# mate_a.net
KiCad netlist of a schematic drawn in EAGLE
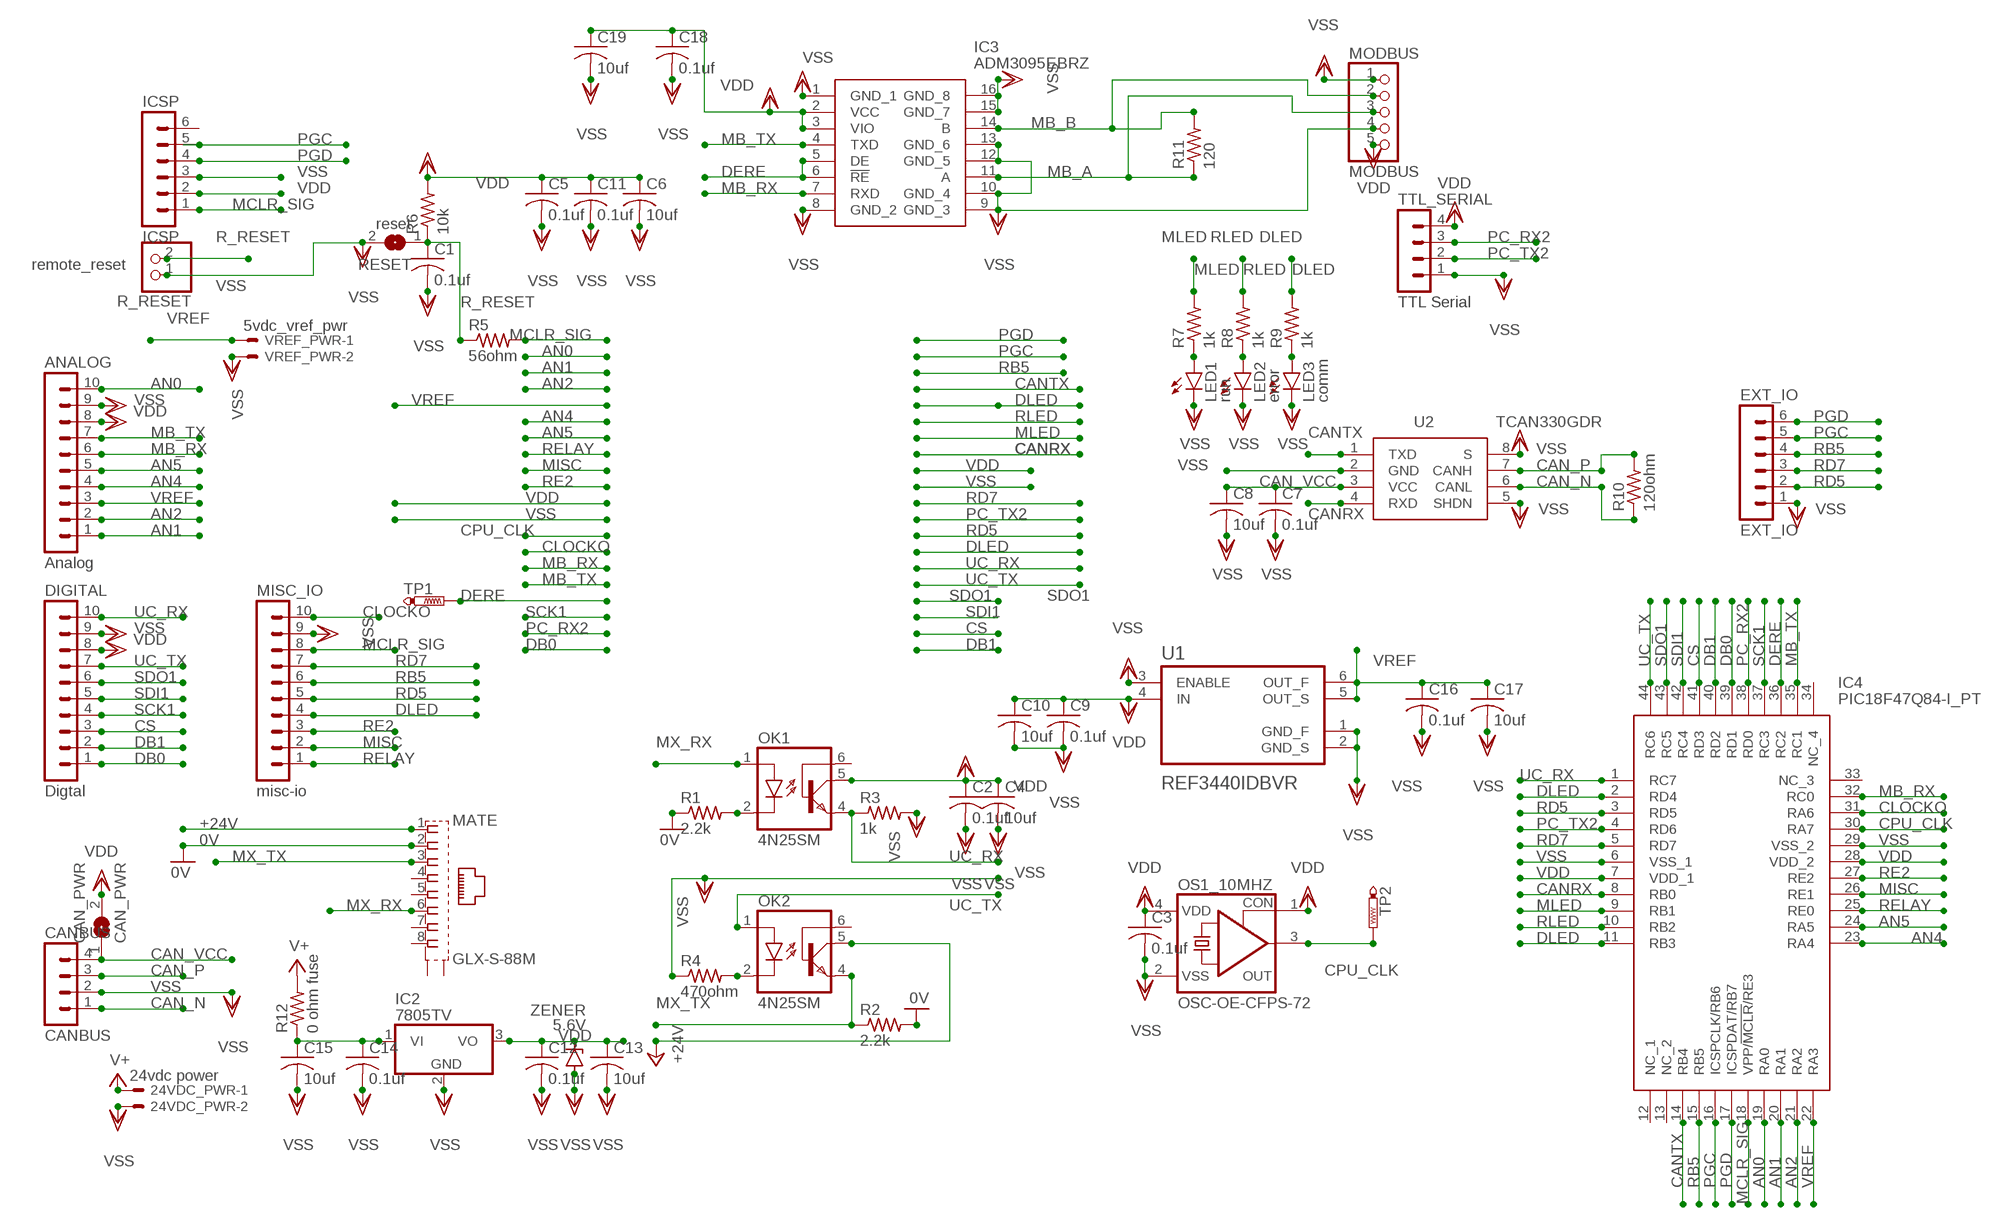
[diagram p0: schematic, sheet 1]

(export (version "E")
  (design (tool "Eeschema 10.0.6"))
  (components
    (comp (ref "24VDC_PWR")
      (value "24vdc power")
      (footprint "eagle-import:22-23-2021")
      (fields (field (name "MF") "MOLEX") (field (name "MPN") "22-23-2021"))
      (libsource (lib "eagle-import") (part "22-23-2021"))
    )
    (comp (ref "ANALOG")
      (value "Analog")
      (footprint "eagle-import:MA10-1")
      (libsource (lib "eagle-import") (part "MA10-1"))
    )
    (comp (ref "C1")
      (value "0.1uf")
      (footprint "eagle-import:C0805")
      (libsource (lib "eagle-import") (part "C-USC0805"))
    )
    (comp (ref "C2")
      (value "0.1uf")
      (footprint "eagle-import:C0805")
      (libsource (lib "eagle-import") (part "C-USC0805"))
    )
    (comp (ref "C3")
      (value "0.1uf")
      (footprint "eagle-import:C0805")
      (libsource (lib "eagle-import") (part "C-USC0805"))
    )
    (comp (ref "C4")
      (value "10uf")
      (footprint "eagle-import:C0805")
      (libsource (lib "eagle-import") (part "C-USC0805"))
    )
    (comp (ref "C5")
      (value "0.1uf")
      (footprint "eagle-import:C0805")
      (libsource (lib "eagle-import") (part "C-USC0805"))
    )
    (comp (ref "C6")
      (value "10uf")
      (footprint "eagle-import:C0805")
      (libsource (lib "eagle-import") (part "C-USC0805"))
    )
    (comp (ref "C7")
      (value "0.1uf")
      (footprint "eagle-import:C0805")
      (libsource (lib "eagle-import") (part "C-USC0805"))
    )
    (comp (ref "C8")
      (value "10uf")
      (footprint "eagle-import:C0805")
      (libsource (lib "eagle-import") (part "C-USC0805"))
    )
    (comp (ref "C9")
      (value "0.1uf")
      (footprint "eagle-import:C0805")
      (libsource (lib "eagle-import") (part "C-USC0805"))
    )
    (comp (ref "C10")
      (value "10uf")
      (footprint "eagle-import:C0805")
      (libsource (lib "eagle-import") (part "C-USC0805"))
    )
    (comp (ref "C11")
      (value "0.1uf")
      (footprint "eagle-import:C0805")
      (libsource (lib "eagle-import") (part "C-USC0805"))
    )
    (comp (ref "C12")
      (value "0.1uf")
      (footprint "eagle-import:C0805")
      (libsource (lib "eagle-import") (part "C-USC0805"))
    )
    (comp (ref "C13")
      (value "10uf")
      (footprint "eagle-import:C0805")
      (libsource (lib "eagle-import") (part "C-USC0805"))
    )
    (comp (ref "C14")
      (value "0.1uf")
      (footprint "eagle-import:C0805")
      (libsource (lib "eagle-import") (part "C-USC0805"))
    )
    (comp (ref "C15")
      (value "10uf")
      (footprint "eagle-import:C0805")
      (libsource (lib "eagle-import") (part "C-USC0805"))
    )
    (comp (ref "C16")
      (value "0.1uf")
      (footprint "eagle-import:C0805")
      (libsource (lib "eagle-import") (part "C-USC0805"))
    )
    (comp (ref "C17")
      (value "10uf")
      (footprint "eagle-import:C0805")
      (libsource (lib "eagle-import") (part "C-USC0805"))
    )
    (comp (ref "C18")
      (value "0.1uf")
      (footprint "eagle-import:C0805")
      (libsource (lib "eagle-import") (part "C-USC0805"))
    )
    (comp (ref "C19")
      (value "10uf")
      (footprint "eagle-import:C0805")
      (libsource (lib "eagle-import") (part "C-USC0805"))
    )
    (comp (ref "CANBUS")
      (value "CANBUS")
      (footprint "eagle-import:MA04-1")
      (libsource (lib "eagle-import") (part "MA04-1"))
    )
    (comp (ref "CAN_PWR")
      (value "CAN_PWR")
      (footprint "eagle-import:SJ")
      (libsource (lib "eagle-import") (part "SJ"))
    )
    (comp (ref "DIGITAL")
      (value "Digtal")
      (footprint "eagle-import:MA10-1")
      (libsource (lib "eagle-import") (part "MA10-1"))
    )
    (comp (ref "EXT_IO")
      (value "EXT_IO")
      (footprint "eagle-import:MA06-1")
      (libsource (lib "eagle-import") (part "MA06-1"))
    )
    (comp (ref "IC2")
      (value "7805TV")
      (footprint "eagle-import:TO220V")
      (libsource (lib "eagle-import") (part "78TV05"))
    )
    (comp (ref "IC3")
      (value "ADM3095EBRZ")
      (footprint "eagle-import:SOIC127P600X175-16N")
      (fields (field (name "MOUSER_PART_NUMBER") "584-ADM3095EBRZ"))
      (libsource (lib "eagle-import") (part "ADM3095EBRZ"))
    )
    (comp (ref "IC4")
      (value "PIC18F47Q84-I_PT")
      (footprint "eagle-import:QFP80P1200X1200X120-44N")
      (fields
        (field (name "MANUFACTURER_PART_NUMBER") "PIC18F47Q84-I/PT")
        (field (name "MOUSER_PART_NUMBER") "579-PIC18F47Q84-I/PT")
      )
      (libsource (lib "eagle-import") (part "PIC18F47Q84-I_PT"))
    )
    (comp (ref "ICSP")
      (value "ICSP")
      (footprint "eagle-import:MA06-1")
      (libsource (lib "eagle-import") (part "MA06-1"))
    )
    (comp (ref "LED1")
      (value "run")
      (footprint "eagle-import:CHIPLED_0805")
      (libsource (lib "eagle-import") (part "LEDCHIPLED_0805"))
    )
    (comp (ref "LED2")
      (value "error")
      (footprint "eagle-import:CHIPLED_0805")
      (libsource (lib "eagle-import") (part "LEDCHIPLED_0805"))
    )
    (comp (ref "LED3")
      (value "comm")
      (footprint "eagle-import:CHIPLED_0805")
      (libsource (lib "eagle-import") (part "LEDCHIPLED_0805"))
    )
    (comp (ref "MATE")
      (value "GLX-S-88M")
      (footprint "eagle-import:GLX-S-88M")
      (libsource (lib "eagle-import") (part "GLX-S-88M"))
    )
    (comp (ref "MISC_IO")
      (value "misc-io")
      (footprint "eagle-import:MA10-1")
      (libsource (lib "eagle-import") (part "MA10-1"))
    )
    (comp (ref "MODBUS")
      (value "MODBUS")
      (footprint "eagle-import:1X05")
      (libsource (lib "eagle-import") (part "PINHD-1X5"))
    )
    (comp (ref "OK1")
      (value "4N25SM")
      (footprint "eagle-import:DIL6-SMD")
      (fields (field (name "MF") "FAIRCHILD SEMICONDUCTOR"))
      (libsource (lib "eagle-import") (part "4N?MS25"))
    )
    (comp (ref "OK2")
      (value "4N25SM")
      (footprint "eagle-import:DIL6-SMD")
      (fields (field (name "MF") "FAIRCHILD SEMICONDUCTOR"))
      (libsource (lib "eagle-import") (part "4N?MS25"))
    )
    (comp (ref "OS1_10MHZ")
      (value "OSC-OE-CFPS-72")
      (footprint "eagle-import:7.2X5.2-4-PAD")
      (libsource (lib "eagle-import") (part "OSC-OE-CFPS-72"))
    )
    (comp (ref "R1")
      (value "2.2k")
      (footprint "eagle-import:R0805")
      (libsource (lib "eagle-import") (part "R-US_R0805"))
    )
    (comp (ref "R2")
      (value "2.2k")
      (footprint "eagle-import:R0805")
      (libsource (lib "eagle-import") (part "R-US_R0805"))
    )
    (comp (ref "R3")
      (value "1k")
      (footprint "eagle-import:R0805")
      (libsource (lib "eagle-import") (part "R-US_R0805"))
    )
    (comp (ref "R4")
      (value "470ohm")
      (footprint "eagle-import:R0805")
      (libsource (lib "eagle-import") (part "R-US_R0805"))
    )
    (comp (ref "R5")
      (value "56ohm")
      (footprint "eagle-import:R0805")
      (libsource (lib "eagle-import") (part "R-US_R0805"))
    )
    (comp (ref "R6")
      (value "10k")
      (footprint "eagle-import:R0805")
      (libsource (lib "eagle-import") (part "R-US_R0805"))
    )
    (comp (ref "R7")
      (value "1k")
      (footprint "eagle-import:R0805")
      (libsource (lib "eagle-import") (part "R-US_R0805"))
    )
    (comp (ref "R8")
      (value "1k")
      (footprint "eagle-import:R0805")
      (libsource (lib "eagle-import") (part "R-US_R0805"))
    )
    (comp (ref "R9")
      (value "1k")
      (footprint "eagle-import:R0805")
      (libsource (lib "eagle-import") (part "R-US_R0805"))
    )
    (comp (ref "R10")
      (value "120ohm")
      (footprint "eagle-import:R0805")
      (libsource (lib "eagle-import") (part "R-US_R0805"))
    )
    (comp (ref "R11")
      (value "120")
      (footprint "eagle-import:R0805")
      (libsource (lib "eagle-import") (part "R-US_R0805"))
    )
    (comp (ref "R12")
      (value "0 ohm fuse")
      (footprint "eagle-import:R1206")
      (libsource (lib "eagle-import") (part "R-US_R1206"))
    )
    (comp (ref "RESET")
      (value "reset")
      (footprint "eagle-import:SJ")
      (libsource (lib "eagle-import") (part "SJ"))
    )
    (comp (ref "R_RESET")
      (value "remote_reset")
      (footprint "eagle-import:1X02")
      (libsource (lib "eagle-import") (part "PINHD-1X2"))
    )
    (comp (ref "TP1")
      (value "PTR1PAD1-13")
      (footprint "eagle-import:P1-13")
      (libsource (lib "eagle-import") (part "PTR1PAD1-13"))
    )
    (comp (ref "TP2")
      (value "PTR1PAD1-13")
      (footprint "eagle-import:P1-13")
      (libsource (lib "eagle-import") (part "PTR1PAD1-13"))
    )
    (comp (ref "TTL_SERIAL")
      (value "TTL Serial")
      (footprint "eagle-import:MA04-1")
      (libsource (lib "eagle-import") (part "MA04-1"))
    )
    (comp (ref "U1")
      (value "REF3440IDBVR")
      (footprint "eagle-import:SOT95P280X145-6N")
      (fields (field (name "MF") "Texas Instruments"))
      (libsource (lib "eagle-import") (part "REF3440IDBVR"))
    )
    (comp (ref "U2")
      (value "TCAN330GDR")
      (footprint "eagle-import:SOIC127P600X175-8N")
      (fields (field (name "MOUSER_PART_NUMBER") "595-TCAN330GDR"))
      (libsource (lib "eagle-import") (part "TCAN330GDR"))
    )
    (comp (ref "VREF_PWR")
      (value "5vdc_vref_pwr")
      (footprint "eagle-import:22-23-2021")
      (fields (field (name "MF") "MOLEX") (field (name "MPN") "22-23-2021"))
      (libsource (lib "eagle-import") (part "22-23-2021"))
    )
    (comp (ref "ZENER")
      (value "5.6V")
      (footprint "eagle-import:SMB")
      (libsource (lib "eagle-import") (part "ZENER-DIODESMB"))
    )
  )
  (nets
    (net (code "1") (name "+24V") (class "Default")
      (node (ref "MATE") (pin "1") (pinfunction "1_1") (pintype "passive"))
      (node (ref "OK2") (pin "5") (pinfunction "COL_5") (pintype "passive"))
    )
    (net (code "2") (name "/AN0") (class "Default")
      (node (ref "ANALOG") (pin "10") (pinfunction "10_10") (pintype "passive"))
      (node (ref "IC4") (pin "19") (pinfunction "RA0_19") (pintype "bidirectional"))
    )
    (net (code "3") (name "/AN1") (class "Default")
      (node (ref "ANALOG") (pin "1") (pinfunction "1_1") (pintype "passive"))
      (node (ref "IC4") (pin "20") (pinfunction "RA1_20") (pintype "bidirectional"))
    )
    (net (code "4") (name "/AN2") (class "Default")
      (node (ref "ANALOG") (pin "2") (pinfunction "2_2") (pintype "passive"))
      (node (ref "IC4") (pin "21") (pinfunction "RA2_21") (pintype "bidirectional"))
    )
    (net (code "5") (name "/AN4") (class "Default")
      (node (ref "ANALOG") (pin "4") (pinfunction "4_4") (pintype "passive"))
      (node (ref "IC4") (pin "23") (pinfunction "RA4_23") (pintype "bidirectional"))
    )
    (net (code "6") (name "/AN5") (class "Default")
      (node (ref "ANALOG") (pin "5") (pinfunction "5_5") (pintype "passive"))
      (node (ref "IC4") (pin "24") (pinfunction "RA5_24") (pintype "bidirectional"))
    )
    (net (code "7") (name "/CANRX") (class "Default")
      (node (ref "IC4") (pin "8") (pinfunction "RB0_8") (pintype "bidirectional"))
      (node (ref "U2") (pin "4") (pinfunction "RXD_4") (pintype "output"))
    )
    (net (code "8") (name "/CANTX") (class "Default")
      (node (ref "IC4") (pin "14") (pinfunction "RB4_14") (pintype "bidirectional"))
      (node (ref "U2") (pin "1") (pinfunction "TXD_1") (pintype "input"))
    )
    (net (code "9") (name "/CAN_N") (class "Default")
      (node (ref "CANBUS") (pin "1") (pinfunction "1_1") (pintype "passive"))
      (node (ref "R10") (pin "1") (pinfunction "1_1") (pintype "passive"))
      (node (ref "U2") (pin "6") (pinfunction "CANL_6") (pintype "bidirectional"))
    )
    (net (code "10") (name "/CAN_P") (class "Default")
      (node (ref "CANBUS") (pin "3") (pinfunction "3_3") (pintype "passive"))
      (node (ref "R10") (pin "2") (pinfunction "2_2") (pintype "passive"))
      (node (ref "U2") (pin "7") (pinfunction "CANH_7") (pintype "bidirectional"))
    )
    (net (code "11") (name "/CAN_VCC") (class "Default")
      (node (ref "C7") (pin "1") (pinfunction "1_1") (pintype "passive"))
      (node (ref "C8") (pin "1") (pinfunction "1_1") (pintype "passive"))
      (node (ref "CANBUS") (pin "4") (pinfunction "4_4") (pintype "passive"))
      (node (ref "CAN_PWR") (pin "1") (pinfunction "1_1") (pintype "passive"))
      (node (ref "U2") (pin "3") (pinfunction "VCC_3") (pintype "power_in"))
    )
    (net (code "12") (name "/CLOCKO") (class "Default")
      (node (ref "IC4") (pin "31") (pinfunction "RA6_31") (pintype "bidirectional"))
      (node (ref "MISC_IO") (pin "10") (pinfunction "10_10") (pintype "passive"))
    )
    (net (code "13") (name "/CPU_CLK") (class "Default")
      (node (ref "IC4") (pin "30") (pinfunction "RA7_30") (pintype "bidirectional"))
      (node (ref "OS1_10MHZ") (pin "3") (pinfunction "OUT_3") (pintype "output"))
      (node (ref "TP2") (pin "TP") (pinfunction "TP_TP") (pintype "input"))
    )
    (net (code "14") (name "/CS") (class "Default")
      (node (ref "DIGITAL") (pin "3") (pinfunction "3_3") (pintype "passive"))
      (node (ref "IC4") (pin "41") (pinfunction "RD3_41") (pintype "bidirectional"))
    )
    (net (code "15") (name "/DB0") (class "Default")
      (node (ref "DIGITAL") (pin "1") (pinfunction "1_1") (pintype "passive"))
      (node (ref "IC4") (pin "39") (pinfunction "RD1_39") (pintype "bidirectional"))
    )
    (net (code "16") (name "/DB1") (class "Default")
      (node (ref "DIGITAL") (pin "2") (pinfunction "2_2") (pintype "passive"))
      (node (ref "IC4") (pin "40") (pinfunction "RD2_40") (pintype "bidirectional"))
    )
    (net (code "17") (name "/DERE") (class "Default")
      (node (ref "IC3") (pin "5") (pinfunction "DE_5") (pintype "input"))
      (node (ref "IC3") (pin "6") (pinfunction "~{RE}_6") (pintype "input"))
      (node (ref "IC4") (pin "36") (pinfunction "RC2_36") (pintype "bidirectional"))
      (node (ref "TP1") (pin "TP") (pinfunction "TP_TP") (pintype "input"))
    )
    (net (code "18") (name "/DLED") (class "Default")
      (node (ref "IC4") (pin "11") (pinfunction "RB3_11") (pintype "bidirectional"))
      (node (ref "IC4") (pin "2") (pinfunction "RD4_2") (pintype "bidirectional"))
      (node (ref "MISC_IO") (pin "4") (pinfunction "4_4") (pintype "passive"))
      (node (ref "R9") (pin "2") (pinfunction "2_2") (pintype "passive"))
    )
    (net (code "19") (name "/MB_A") (class "Default")
      (node (ref "IC3") (pin "11") (pinfunction "A_11") (pintype "bidirectional"))
      (node (ref "MODBUS") (pin "3") (pinfunction "3_3") (pintype "passive"))
      (node (ref "R11") (pin "1") (pinfunction "1_1") (pintype "passive"))
    )
    (net (code "20") (name "/MB_B") (class "Default")
      (node (ref "IC3") (pin "14") (pinfunction "B_14") (pintype "bidirectional"))
      (node (ref "MODBUS") (pin "2") (pinfunction "2_2") (pintype "passive"))
      (node (ref "R11") (pin "2") (pinfunction "2_2") (pintype "passive"))
    )
    (net (code "21") (name "/MB_RX") (class "Default")
      (node (ref "ANALOG") (pin "6") (pinfunction "6_6") (pintype "passive"))
      (node (ref "IC3") (pin "7") (pinfunction "RXD_7") (pintype "output"))
      (node (ref "IC4") (pin "32") (pinfunction "RC0_32") (pintype "bidirectional"))
    )
    (net (code "22") (name "/MB_TX") (class "Default")
      (node (ref "ANALOG") (pin "7") (pinfunction "7_7") (pintype "passive"))
      (node (ref "IC3") (pin "4") (pinfunction "TXD_4") (pintype "input"))
      (node (ref "IC4") (pin "35") (pinfunction "RC1_35") (pintype "bidirectional"))
    )
    (net (code "23") (name "/MCLR_SIG") (class "Default")
      (node (ref "IC4") (pin "18") (pinfunction "VPP/~{MCLR}/RE3_18") (pintype "bidirectional"))
      (node (ref "ICSP") (pin "1") (pinfunction "1_1") (pintype "passive"))
      (node (ref "MISC_IO") (pin "8") (pinfunction "8_8") (pintype "passive"))
      (node (ref "R5") (pin "2") (pinfunction "2_2") (pintype "passive"))
    )
    (net (code "24") (name "/MISC") (class "Default")
      (node (ref "IC4") (pin "26") (pinfunction "RE1_26") (pintype "bidirectional"))
      (node (ref "MISC_IO") (pin "2") (pinfunction "2_2") (pintype "passive"))
    )
    (net (code "25") (name "/MLED") (class "Default")
      (node (ref "IC4") (pin "9") (pinfunction "RB1_9") (pintype "bidirectional"))
      (node (ref "R7") (pin "2") (pinfunction "2_2") (pintype "passive"))
    )
    (net (code "26") (name "/MX_RX") (class "Default")
      (node (ref "MATE") (pin "6") (pinfunction "6_6") (pintype "passive"))
      (node (ref "OK1") (pin "1") (pinfunction "A_1") (pintype "passive"))
    )
    (net (code "27") (name "/MX_TX") (class "Default")
      (node (ref "MATE") (pin "3") (pinfunction "3_3") (pintype "passive"))
      (node (ref "OK2") (pin "4") (pinfunction "EMI_4") (pintype "passive"))
      (node (ref "R2") (pin "1") (pinfunction "1_1") (pintype "passive"))
    )
    (net (code "28") (name "/PC_RX2") (class "Default")
      (node (ref "IC4") (pin "38") (pinfunction "RD0_38") (pintype "bidirectional"))
      (node (ref "TTL_SERIAL") (pin "3") (pinfunction "3_3") (pintype "passive"))
    )
    (net (code "29") (name "/PC_TX2") (class "Default")
      (node (ref "IC4") (pin "4") (pinfunction "RD6_4") (pintype "bidirectional"))
      (node (ref "TTL_SERIAL") (pin "2") (pinfunction "2_2") (pintype "passive"))
    )
    (net (code "30") (name "/PGC") (class "Default")
      (node (ref "EXT_IO") (pin "5") (pinfunction "5_5") (pintype "passive"))
      (node (ref "IC4") (pin "16") (pinfunction "ICSPCLK/RB6_16") (pintype "bidirectional"))
      (node (ref "ICSP") (pin "5") (pinfunction "5_5") (pintype "passive"))
    )
    (net (code "31") (name "/PGD") (class "Default")
      (node (ref "EXT_IO") (pin "6") (pinfunction "6_6") (pintype "passive"))
      (node (ref "IC4") (pin "17") (pinfunction "ICSPDAT/RB7_17") (pintype "bidirectional"))
      (node (ref "ICSP") (pin "4") (pinfunction "4_4") (pintype "passive"))
    )
    (net (code "32") (name "/RB5") (class "Default")
      (node (ref "EXT_IO") (pin "4") (pinfunction "4_4") (pintype "passive"))
      (node (ref "IC4") (pin "15") (pinfunction "RB5_15") (pintype "bidirectional"))
      (node (ref "MISC_IO") (pin "6") (pinfunction "6_6") (pintype "passive"))
    )
    (net (code "33") (name "/RD5") (class "Default")
      (node (ref "EXT_IO") (pin "2") (pinfunction "2_2") (pintype "passive"))
      (node (ref "IC4") (pin "3") (pinfunction "RD5_3") (pintype "bidirectional"))
      (node (ref "MISC_IO") (pin "5") (pinfunction "5_5") (pintype "passive"))
    )
    (net (code "34") (name "/RD7") (class "Default")
      (node (ref "EXT_IO") (pin "3") (pinfunction "3_3") (pintype "passive"))
      (node (ref "IC4") (pin "5") (pinfunction "RD7_5") (pintype "bidirectional"))
      (node (ref "MISC_IO") (pin "7") (pinfunction "7_7") (pintype "passive"))
    )
    (net (code "35") (name "/RE2") (class "Default")
      (node (ref "IC4") (pin "27") (pinfunction "RE2_27") (pintype "bidirectional"))
      (node (ref "MISC_IO") (pin "3") (pinfunction "3_3") (pintype "passive"))
    )
    (net (code "36") (name "/RELAY") (class "Default")
      (node (ref "IC4") (pin "25") (pinfunction "RE0_25") (pintype "bidirectional"))
      (node (ref "MISC_IO") (pin "1") (pinfunction "1_1") (pintype "passive"))
    )
    (net (code "37") (name "/RLED") (class "Default")
      (node (ref "IC4") (pin "10") (pinfunction "RB2_10") (pintype "bidirectional"))
      (node (ref "R8") (pin "2") (pinfunction "2_2") (pintype "passive"))
    )
    (net (code "38") (name "/R_RESET") (class "Default")
      (node (ref "C1") (pin "1") (pinfunction "1_1") (pintype "passive"))
      (node (ref "R5") (pin "1") (pinfunction "1_1") (pintype "passive"))
      (node (ref "R6") (pin "1") (pinfunction "1_1") (pintype "passive"))
      (node (ref "RESET") (pin "1") (pinfunction "1_1") (pintype "passive"))
      (node (ref "R_RESET") (pin "2") (pinfunction "2_2") (pintype "passive"))
    )
    (net (code "39") (name "/SCK1") (class "Default")
      (node (ref "DIGITAL") (pin "4") (pinfunction "4_4") (pintype "passive"))
      (node (ref "IC4") (pin "37") (pinfunction "RC3_37") (pintype "bidirectional"))
    )
    (net (code "40") (name "/SDI1") (class "Default")
      (node (ref "DIGITAL") (pin "5") (pinfunction "5_5") (pintype "passive"))
      (node (ref "IC4") (pin "42") (pinfunction "RC4_42") (pintype "bidirectional"))
    )
    (net (code "41") (name "/SDO1") (class "Default")
      (node (ref "DIGITAL") (pin "6") (pinfunction "6_6") (pintype "passive"))
      (node (ref "IC4") (pin "43") (pinfunction "RC5_43") (pintype "bidirectional"))
    )
    (net (code "42") (name "/UC_RX") (class "Default")
      (node (ref "DIGITAL") (pin "10") (pinfunction "10_10") (pintype "passive"))
      (node (ref "IC4") (pin "1") (pinfunction "RC7_1") (pintype "bidirectional"))
      (node (ref "OK1") (pin "4") (pinfunction "EMI_4") (pintype "passive"))
      (node (ref "R3") (pin "1") (pinfunction "1_1") (pintype "passive"))
    )
    (net (code "43") (name "/UC_TX") (class "Default")
      (node (ref "DIGITAL") (pin "7") (pinfunction "7_7") (pintype "passive"))
      (node (ref "IC4") (pin "44") (pinfunction "RC6_44") (pintype "bidirectional"))
      (node (ref "OK2") (pin "1") (pinfunction "A_1") (pintype "passive"))
    )
    (net (code "44") (name "/VREF") (class "Default")
      (node (ref "ANALOG") (pin "3") (pinfunction "3_3") (pintype "passive"))
      (node (ref "C16") (pin "1") (pinfunction "1_1") (pintype "passive"))
      (node (ref "C17") (pin "1") (pinfunction "1_1") (pintype "passive"))
      (node (ref "IC4") (pin "22") (pinfunction "RA3_22") (pintype "bidirectional"))
      (node (ref "U1") (pin "5") (pinfunction "OUT_S_5") (pintype "output"))
      (node (ref "U1") (pin "6") (pinfunction "OUT_F_6") (pintype "output"))
      (node (ref "VREF_PWR") (pin "1") (pinfunction "S_1") (pintype "passive"))
    )
    (net (code "45") (name "0V") (class "Default")
      (node (ref "MATE") (pin "2") (pinfunction "2_2") (pintype "passive"))
      (node (ref "R1") (pin "1") (pinfunction "1_1") (pintype "passive"))
      (node (ref "R2") (pin "2") (pinfunction "2_2") (pintype "passive"))
    )
    (net (code "46") (name "Net-(IC2-VI)") (class "Default")
      (node (ref "C14") (pin "1") (pinfunction "1_1") (pintype "passive"))
      (node (ref "C15") (pin "1") (pinfunction "1_1") (pintype "passive"))
      (node (ref "IC2") (pin "1") (pinfunction "VI_1") (pintype "input"))
      (node (ref "R12") (pin "1") (pinfunction "1_1") (pintype "passive"))
    )
    (net (code "47") (name "Net-(LED1-PadA)") (class "Default")
      (node (ref "LED1") (pin "A") (pinfunction "A_A") (pintype "passive"))
      (node (ref "R7") (pin "1") (pinfunction "1_1") (pintype "passive"))
    )
    (net (code "48") (name "Net-(LED2-PadA)") (class "Default")
      (node (ref "LED2") (pin "A") (pinfunction "A_A") (pintype "passive"))
      (node (ref "R8") (pin "1") (pinfunction "1_1") (pintype "passive"))
    )
    (net (code "49") (name "Net-(LED3-PadA)") (class "Default")
      (node (ref "LED3") (pin "A") (pinfunction "A_A") (pintype "passive"))
      (node (ref "R9") (pin "1") (pinfunction "1_1") (pintype "passive"))
    )
    (net (code "50") (name "Net-(OK1-C)") (class "Default")
      (node (ref "OK1") (pin "2") (pinfunction "C_2") (pintype "passive"))
      (node (ref "R1") (pin "2") (pinfunction "2_2") (pintype "passive"))
    )
    (net (code "51") (name "Net-(OK2-C)") (class "Default")
      (node (ref "OK2") (pin "2") (pinfunction "C_2") (pintype "passive"))
      (node (ref "R4") (pin "2") (pinfunction "2_2") (pintype "passive"))
    )
    (net (code "52") (name "V+") (class "Default")
      (node (ref "24VDC_PWR") (pin "1") (pinfunction "S_1") (pintype "passive"))
      (node (ref "R12") (pin "2") (pinfunction "2_2") (pintype "passive"))
    )
    (net (code "53") (name "VDD") (class "Default")
      (node (ref "ANALOG") (pin "8") (pinfunction "8_8") (pintype "passive"))
      (node (ref "C10") (pin "1") (pinfunction "1_1") (pintype "passive"))
      (node (ref "C11") (pin "1") (pinfunction "1_1") (pintype "passive"))
      (node (ref "C12") (pin "1") (pinfunction "1_1") (pintype "passive"))
      (node (ref "C13") (pin "1") (pinfunction "1_1") (pintype "passive"))
      (node (ref "C18") (pin "1") (pinfunction "1_1") (pintype "passive"))
      (node (ref "C19") (pin "1") (pinfunction "1_1") (pintype "passive"))
      (node (ref "C2") (pin "1") (pinfunction "1_1") (pintype "passive"))
      (node (ref "C3") (pin "1") (pinfunction "1_1") (pintype "passive"))
      (node (ref "C4") (pin "1") (pinfunction "1_1") (pintype "passive"))
      (node (ref "C5") (pin "1") (pinfunction "1_1") (pintype "passive"))
      (node (ref "C6") (pin "1") (pinfunction "1_1") (pintype "passive"))
      (node (ref "C9") (pin "1") (pinfunction "1_1") (pintype "passive"))
      (node (ref "CAN_PWR") (pin "2") (pinfunction "2_2") (pintype "passive"))
      (node (ref "DIGITAL") (pin "8") (pinfunction "8_8") (pintype "passive"))
      (node (ref "IC2") (pin "3") (pinfunction "VO_3") (pintype "passive"))
      (node (ref "IC3") (pin "2") (pinfunction "VCC_2") (pintype "power_in"))
      (node (ref "IC3") (pin "3") (pinfunction "VIO_3") (pintype "power_in"))
      (node (ref "IC4") (pin "28") (pinfunction "VDD_2_28") (pintype "bidirectional"))
      (node (ref "IC4") (pin "7") (pinfunction "VDD_1_7") (pintype "bidirectional"))
      (node (ref "ICSP") (pin "2") (pinfunction "2_2") (pintype "passive"))
      (node (ref "MODBUS") (pin "5") (pinfunction "5_5") (pintype "passive"))
      (node (ref "OK1") (pin "5") (pinfunction "COL_5") (pintype "passive"))
      (node (ref "OS1_10MHZ") (pin "1") (pinfunction "CON_1") (pintype "input"))
      (node (ref "OS1_10MHZ") (pin "4") (pinfunction "VDD_4") (pintype "power_in"))
      (node (ref "R6") (pin "2") (pinfunction "2_2") (pintype "passive"))
      (node (ref "TTL_SERIAL") (pin "4") (pinfunction "4_4") (pintype "passive"))
      (node (ref "U1") (pin "4") (pinfunction "IN_4") (pintype "input"))
      (node (ref "ZENER") (pin "C") (pinfunction "C_C") (pintype "passive"))
    )
    (net (code "54") (name "VSS") (class "Default")
      (node (ref "24VDC_PWR") (pin "2") (pinfunction "S_2") (pintype "passive"))
      (node (ref "ANALOG") (pin "9") (pinfunction "9_9") (pintype "passive"))
      (node (ref "C1") (pin "2") (pinfunction "2_2") (pintype "passive"))
      (node (ref "C10") (pin "2") (pinfunction "2_2") (pintype "passive"))
      (node (ref "C11") (pin "2") (pinfunction "2_2") (pintype "passive"))
      (node (ref "C12") (pin "2") (pinfunction "2_2") (pintype "passive"))
      (node (ref "C13") (pin "2") (pinfunction "2_2") (pintype "passive"))
      (node (ref "C14") (pin "2") (pinfunction "2_2") (pintype "passive"))
      (node (ref "C15") (pin "2") (pinfunction "2_2") (pintype "passive"))
      (node (ref "C16") (pin "2") (pinfunction "2_2") (pintype "passive"))
      (node (ref "C17") (pin "2") (pinfunction "2_2") (pintype "passive"))
      (node (ref "C18") (pin "2") (pinfunction "2_2") (pintype "passive"))
      (node (ref "C19") (pin "2") (pinfunction "2_2") (pintype "passive"))
      (node (ref "C2") (pin "2") (pinfunction "2_2") (pintype "passive"))
      (node (ref "C3") (pin "2") (pinfunction "2_2") (pintype "passive"))
      (node (ref "C4") (pin "2") (pinfunction "2_2") (pintype "passive"))
      (node (ref "C5") (pin "2") (pinfunction "2_2") (pintype "passive"))
      (node (ref "C6") (pin "2") (pinfunction "2_2") (pintype "passive"))
      (node (ref "C7") (pin "2") (pinfunction "2_2") (pintype "passive"))
      (node (ref "C8") (pin "2") (pinfunction "2_2") (pintype "passive"))
      (node (ref "C9") (pin "2") (pinfunction "2_2") (pintype "passive"))
      (node (ref "CANBUS") (pin "2") (pinfunction "2_2") (pintype "passive"))
      (node (ref "DIGITAL") (pin "9") (pinfunction "9_9") (pintype "passive"))
      (node (ref "EXT_IO") (pin "1") (pinfunction "1_1") (pintype "passive"))
      (node (ref "IC2") (pin "2") (pinfunction "GND_2") (pintype "passive"))
      (node (ref "IC3") (pin "1") (pinfunction "GND_1_1") (pintype "power_in"))
      (node (ref "IC3") (pin "10") (pinfunction "GND_4_10") (pintype "power_in"))
      (node (ref "IC3") (pin "12") (pinfunction "GND_5_12") (pintype "power_in"))
      (node (ref "IC3") (pin "13") (pinfunction "GND_6_13") (pintype "power_in"))
      (node (ref "IC3") (pin "15") (pinfunction "GND_7_15") (pintype "power_in"))
      (node (ref "IC3") (pin "16") (pinfunction "GND_8_16") (pintype "power_in"))
      (node (ref "IC3") (pin "8") (pinfunction "GND_2_8") (pintype "power_in"))
      (node (ref "IC3") (pin "9") (pinfunction "GND_3_9") (pintype "power_in"))
      (node (ref "IC4") (pin "29") (pinfunction "VSS_2_29") (pintype "bidirectional"))
      (node (ref "IC4") (pin "6") (pinfunction "VSS_1_6") (pintype "bidirectional"))
      (node (ref "ICSP") (pin "3") (pinfunction "3_3") (pintype "passive"))
      (node (ref "LED1") (pin "C") (pinfunction "C_C") (pintype "passive"))
      (node (ref "LED2") (pin "C") (pinfunction "C_C") (pintype "passive"))
      (node (ref "LED3") (pin "C") (pinfunction "C_C") (pintype "passive"))
      (node (ref "MISC_IO") (pin "9") (pinfunction "9_9") (pintype "passive"))
      (node (ref "MODBUS") (pin "1") (pinfunction "1_1") (pintype "passive"))
      (node (ref "MODBUS") (pin "4") (pinfunction "4_4") (pintype "passive"))
      (node (ref "OS1_10MHZ") (pin "2") (pinfunction "VSS_2") (pintype "power_in"))
      (node (ref "R3") (pin "2") (pinfunction "2_2") (pintype "passive"))
      (node (ref "R4") (pin "1") (pinfunction "1_1") (pintype "passive"))
      (node (ref "RESET") (pin "2") (pinfunction "2_2") (pintype "passive"))
      (node (ref "R_RESET") (pin "1") (pinfunction "1_1") (pintype "passive"))
      (node (ref "TTL_SERIAL") (pin "1") (pinfunction "1_1") (pintype "passive"))
      (node (ref "U1") (pin "1") (pinfunction "GND_F_1") (pintype "power_in"))
      (node (ref "U1") (pin "2") (pinfunction "GND_S_2") (pintype "power_in"))
      (node (ref "U1") (pin "3") (pinfunction "ENABLE_3") (pintype "input"))
      (node (ref "U2") (pin "2") (pinfunction "GND_2") (pintype "power_in"))
      (node (ref "U2") (pin "5") (pinfunction "SHDN_5") (pintype "bidirectional"))
      (node (ref "U2") (pin "8") (pinfunction "S_8") (pintype "bidirectional"))
      (node (ref "VREF_PWR") (pin "2") (pinfunction "S_2") (pintype "passive"))
      (node (ref "ZENER") (pin "A") (pinfunction "A_A") (pintype "passive"))
    )
    (net (code "55") (name "unconnected-(IC4-NC_1-Pad12)") (class "Default")
      (node (ref "IC4") (pin "12") (pinfunction "NC_1_12") (pintype "bidirectional"))
    )
    (net (code "56") (name "unconnected-(IC4-NC_2-Pad13)") (class "Default")
      (node (ref "IC4") (pin "13") (pinfunction "NC_2_13") (pintype "bidirectional"))
    )
    (net (code "57") (name "unconnected-(IC4-NC_3-Pad33)") (class "Default")
      (node (ref "IC4") (pin "33") (pinfunction "NC_3_33") (pintype "bidirectional"))
    )
    (net (code "58") (name "unconnected-(IC4-NC_4-Pad34)") (class "Default")
      (node (ref "IC4") (pin "34") (pinfunction "NC_4_34") (pintype "bidirectional"))
    )
    (net (code "59") (name "unconnected-(ICSP-Pad6)") (class "Default")
      (node (ref "ICSP") (pin "6") (pinfunction "6_6") (pintype "passive"))
    )
    (net (code "60") (name "unconnected-(MATE-Pad4)") (class "Default")
      (node (ref "MATE") (pin "4") (pinfunction "4_4") (pintype "passive"))
    )
    (net (code "61") (name "unconnected-(MATE-Pad5)") (class "Default")
      (node (ref "MATE") (pin "5") (pinfunction "5_5") (pintype "passive"))
    )
    (net (code "62") (name "unconnected-(MATE-Pad7)") (class "Default")
      (node (ref "MATE") (pin "7") (pinfunction "7_7") (pintype "passive"))
    )
    (net (code "63") (name "unconnected-(MATE-Pad8)") (class "Default")
      (node (ref "MATE") (pin "8") (pinfunction "8_8") (pintype "passive"))
    )
    (net (code "64") (name "unconnected-(MATE-PadS1)") (class "Default")
      (node (ref "MATE") (pin "S1") (pinfunction "S1_S1") (pintype "passive"))
    )
    (net (code "65") (name "unconnected-(MATE-PadS2)") (class "Default")
      (node (ref "MATE") (pin "S2") (pinfunction "S2_S2") (pintype "passive"))
    )
    (net (code "66") (name "unconnected-(OK1-BAS-Pad6)") (class "Default")
      (node (ref "OK1") (pin "6") (pinfunction "BAS_6") (pintype "passive"))
    )
    (net (code "67") (name "unconnected-(OK2-BAS-Pad6)") (class "Default")
      (node (ref "OK2") (pin "6") (pinfunction "BAS_6") (pintype "passive"))
    )
  )
)
